# Mozard_Grounded_Touch_Pads.net
KiCad netlist of a schematic drawn in EAGLE
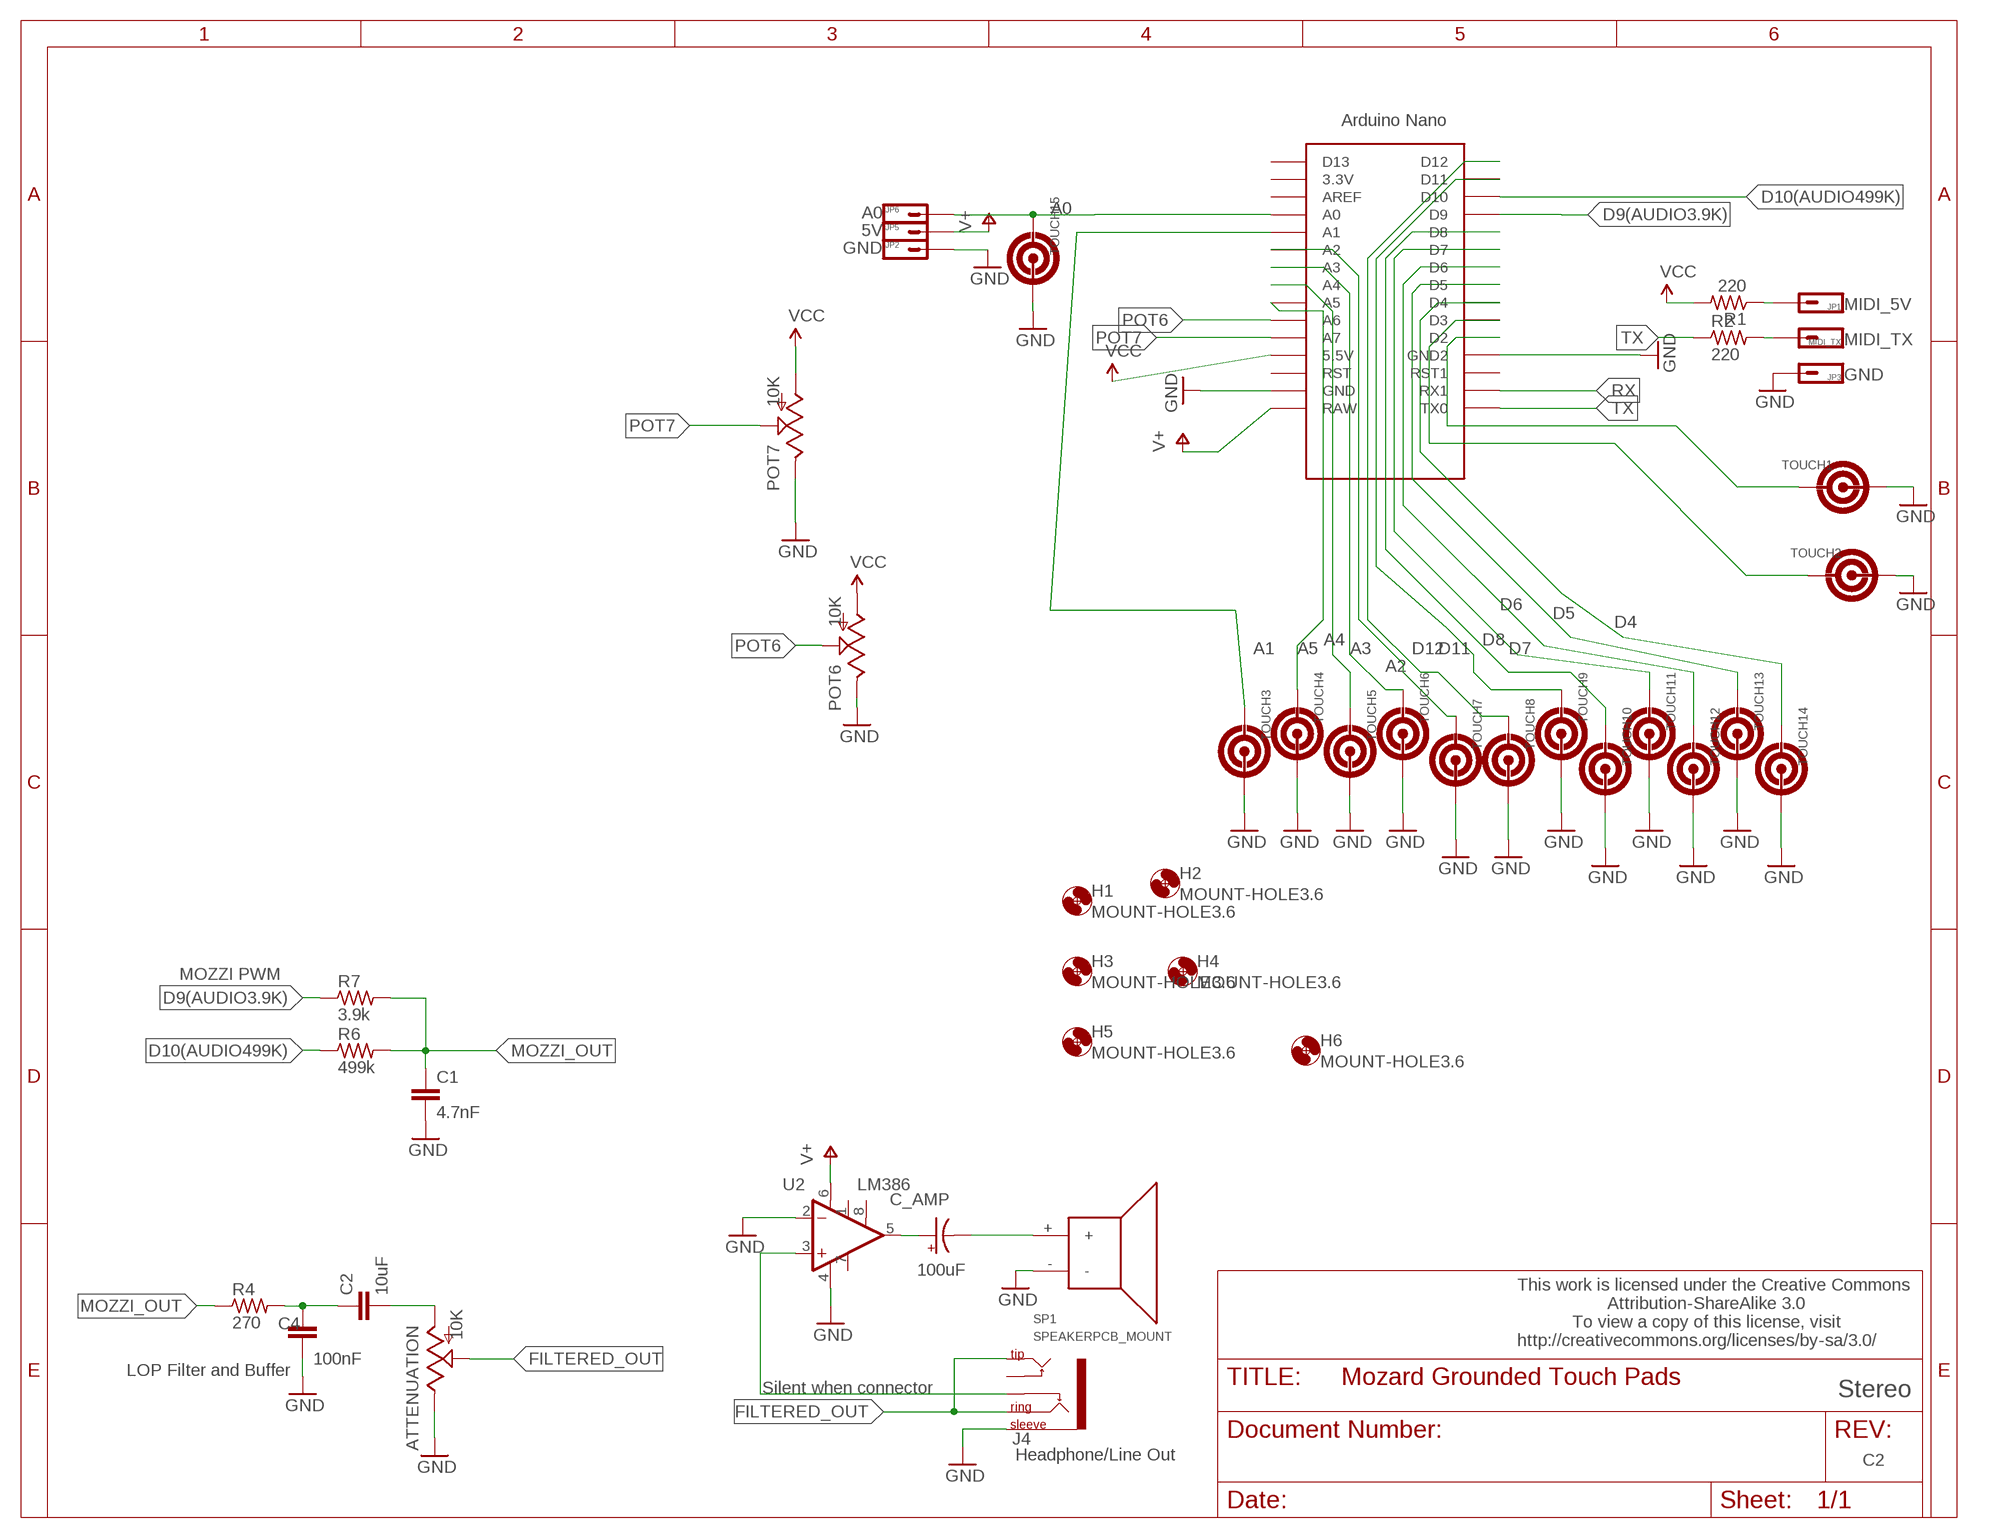
[diagram p0: schematic, sheet 1]

(export (version "E")
  (design (tool "Eeschema 10.0.6"))
  (components
    (comp (ref "ATTENUATION")
      (value "10K")
      (footprint "eagle-import:ALPS_POT_KIT")
      (libsource (lib "eagle-import") (part "POTALPS-KIT"))
    )
    (comp (ref "C1")
      (value "4.7nF")
      (footprint "eagle-import:CAP-PTH-SMALL-KIT")
      (libsource (lib "eagle-import") (part "0.1UF-50V-20%(PTH)KIT-EZ"))
    )
    (comp (ref "C2")
      (value "10uF")
      (footprint "eagle-import:CAP-PTH-SMALL-KIT")
      (libsource (lib "eagle-import") (part "0.1UF-50V-20%(PTH)KIT-EZ"))
    )
    (comp (ref "C4")
      (value "100nF")
      (footprint "eagle-import:CAP-PTH-SMALL-KIT")
      (libsource (lib "eagle-import") (part "0.1UF-50V-20%(PTH)KIT-EZ"))
    )
    (comp (ref "C_AMP")
      (value "100uF")
      (footprint "eagle-import:CPOL-RADIAL-10UF-25V")
      (libsource (lib "eagle-import") (part "CPOL-RADIAL-10UF-25V"))
    )
    (comp (ref "H1")
      (value "MOUNT-HOLE3.6")
      (footprint "eagle-import:3,6")
      (libsource (lib "eagle-import") (part "MOUNT-HOLE3.6"))
    )
    (comp (ref "H2")
      (value "MOUNT-HOLE3.6")
      (footprint "eagle-import:3,6")
      (libsource (lib "eagle-import") (part "MOUNT-HOLE3.6"))
    )
    (comp (ref "H3")
      (value "MOUNT-HOLE3.6")
      (footprint "eagle-import:3,6")
      (libsource (lib "eagle-import") (part "MOUNT-HOLE3.6"))
    )
    (comp (ref "H4")
      (value "MOUNT-HOLE3.6")
      (footprint "eagle-import:3,6")
      (libsource (lib "eagle-import") (part "MOUNT-HOLE3.6"))
    )
    (comp (ref "H5")
      (value "MOUNT-HOLE3.6")
      (footprint "eagle-import:3,6")
      (libsource (lib "eagle-import") (part "MOUNT-HOLE3.6"))
    )
    (comp (ref "H6")
      (value "MOUNT-HOLE3.6")
      (footprint "eagle-import:3,6")
      (libsource (lib "eagle-import") (part "MOUNT-HOLE3.6"))
    )
    (comp (ref "J4")
      (value "Headphone/Line Out")
      (footprint "eagle-import:AUDIO-JACK")
      (libsource (lib "eagle-import") (part "AUDIO-JACKPTH"))
    )
    (comp (ref "JP1")
      (value "MIDI_5V")
      (footprint "eagle-import:1X01_SIDE_NAME")
      (libsource (lib "eagle-import") (part "HEADER-1X1"))
    )
    (comp (ref "JP2")
      (value "GND")
      (footprint "eagle-import:1X01_SIDE_NAME")
      (libsource (lib "eagle-import") (part "HEADER-1X1"))
    )
    (comp (ref "JP3")
      (value "GND")
      (footprint "eagle-import:1X01_SIDE_NAME")
      (libsource (lib "eagle-import") (part "HEADER-1X1"))
    )
    (comp (ref "JP5")
      (value "5V")
      (footprint "eagle-import:1X01_SIDE_NAME")
      (libsource (lib "eagle-import") (part "HEADER-1X1"))
    )
    (comp (ref "JP6")
      (value "A0")
      (footprint "eagle-import:1X01_SIDE_NAME")
      (libsource (lib "eagle-import") (part "HEADER-1X1"))
    )
    (comp (ref "MIDI_TX")
      (value "MIDI_TX")
      (footprint "eagle-import:1X01_SIDE_NAME")
      (libsource (lib "eagle-import") (part "HEADER-1X1"))
    )
    (comp (ref "POT6")
      (value "10K")
      (footprint "eagle-import:ALPS_POT_KIT")
      (libsource (lib "eagle-import") (part "POTALPS-KIT"))
    )
    (comp (ref "POT7")
      (value "10K")
      (footprint "eagle-import:ALPS_POT_KIT")
      (libsource (lib "eagle-import") (part "POTALPS-KIT"))
    )
    (comp (ref "R1")
      (value "220")
      (footprint "eagle-import:0204_7")
      (libsource (lib "eagle-import") (part "R-US_0204/7"))
    )
    (comp (ref "R2")
      (value "220")
      (footprint "eagle-import:0204_7")
      (libsource (lib "eagle-import") (part "R-US_0204/7"))
    )
    (comp (ref "R4")
      (value "270")
      (footprint "eagle-import:0204_7")
      (libsource (lib "eagle-import") (part "R-US_0204/7"))
    )
    (comp (ref "R6")
      (value "499k")
      (footprint "eagle-import:0204_7")
      (libsource (lib "eagle-import") (part "R-US_0204/7"))
    )
    (comp (ref "R7")
      (value "3.9k")
      (footprint "eagle-import:0204_7")
      (libsource (lib "eagle-import") (part "R-US_0204/7"))
    )
    (comp (ref "SP1")
      (value "SPEAKERPCB_MOUNT")
      (footprint "eagle-import:PCB_MOUNT_SPEAKER")
      (fields (field (name "MFG") "SANCO"))
      (libsource (lib "eagle-import") (part "SPEAKERPCB_MOUNT"))
    )
    (comp (ref "TOUCH1")
      (value "PCB-TOUCHPAD2")
      (footprint "eagle-import:PCB-TOUCHPAD2")
      (libsource (lib "eagle-import") (part "PCB-TOUCHPAD2"))
    )
    (comp (ref "TOUCH2")
      (value "PCB-TOUCHPAD2")
      (footprint "eagle-import:PCB-TOUCHPAD2")
      (libsource (lib "eagle-import") (part "PCB-TOUCHPAD2"))
    )
    (comp (ref "TOUCH3")
      (value "PCB-TOUCHPAD2")
      (footprint "eagle-import:PCB-TOUCHPAD2")
      (libsource (lib "eagle-import") (part "PCB-TOUCHPAD2"))
    )
    (comp (ref "TOUCH4")
      (value "PCB-TOUCHPAD2")
      (footprint "eagle-import:PCB-TOUCHPAD2")
      (libsource (lib "eagle-import") (part "PCB-TOUCHPAD2"))
    )
    (comp (ref "TOUCH5")
      (value "PCB-TOUCHPAD2")
      (footprint "eagle-import:PCB-TOUCHPAD2")
      (libsource (lib "eagle-import") (part "PCB-TOUCHPAD2"))
    )
    (comp (ref "TOUCH6")
      (value "PCB-TOUCHPAD2")
      (footprint "eagle-import:PCB-TOUCHPAD2")
      (libsource (lib "eagle-import") (part "PCB-TOUCHPAD2"))
    )
    (comp (ref "TOUCH7")
      (value "PCB-TOUCHPAD2")
      (footprint "eagle-import:PCB-TOUCHPAD2")
      (libsource (lib "eagle-import") (part "PCB-TOUCHPAD2"))
    )
    (comp (ref "TOUCH8")
      (value "PCB-TOUCHPAD2")
      (footprint "eagle-import:PCB-TOUCHPAD2")
      (libsource (lib "eagle-import") (part "PCB-TOUCHPAD2"))
    )
    (comp (ref "TOUCH9")
      (value "PCB-TOUCHPAD2")
      (footprint "eagle-import:PCB-TOUCHPAD2")
      (libsource (lib "eagle-import") (part "PCB-TOUCHPAD2"))
    )
    (comp (ref "TOUCH10")
      (value "PCB-TOUCHPAD2")
      (footprint "eagle-import:PCB-TOUCHPAD2")
      (libsource (lib "eagle-import") (part "PCB-TOUCHPAD2"))
    )
    (comp (ref "TOUCH11")
      (value "PCB-TOUCHPAD2")
      (footprint "eagle-import:PCB-TOUCHPAD2")
      (libsource (lib "eagle-import") (part "PCB-TOUCHPAD2"))
    )
    (comp (ref "TOUCH12")
      (value "PCB-TOUCHPAD2")
      (footprint "eagle-import:PCB-TOUCHPAD2")
      (libsource (lib "eagle-import") (part "PCB-TOUCHPAD2"))
    )
    (comp (ref "TOUCH13")
      (value "PCB-TOUCHPAD2")
      (footprint "eagle-import:PCB-TOUCHPAD2")
      (libsource (lib "eagle-import") (part "PCB-TOUCHPAD2"))
    )
    (comp (ref "TOUCH14")
      (value "PCB-TOUCHPAD2")
      (footprint "eagle-import:PCB-TOUCHPAD2")
      (libsource (lib "eagle-import") (part "PCB-TOUCHPAD2"))
    )
    (comp (ref "TOUCH15")
      (value "PCB-TOUCHPAD2")
      (footprint "eagle-import:PCB-TOUCHPAD2")
      (libsource (lib "eagle-import") (part "PCB-TOUCHPAD2"))
    )
    (comp (ref "U$1")
      (value "NANO")
      (footprint "eagle-import:NANO")
      (libsource (lib "eagle-import") (part "NANO"))
    )
    (comp (ref "U2")
      (value "LM386")
      (footprint "eagle-import:DIP08")
      (libsource (lib "eagle-import") (part "LM386"))
    )
  )
  (nets
    (net (code "1") (name "/A0") (class "Default")
      (node (ref "JP6") (pin "1") (pinfunction "1_1") (pintype "passive"))
      (node (ref "TOUCH15") (pin "1") (pinfunction "1_1") (pintype "bidirectional"))
      (node (ref "U$1") (pin "A0") (pinfunction "A0_A0") (pintype "bidirectional"))
    )
    (net (code "2") (name "/A1") (class "Default")
      (node (ref "TOUCH3") (pin "1") (pinfunction "1_1") (pintype "bidirectional"))
      (node (ref "U$1") (pin "A1") (pinfunction "A1_A1") (pintype "bidirectional"))
    )
    (net (code "3") (name "/A2") (class "Default")
      (node (ref "TOUCH7") (pin "1") (pinfunction "1_1") (pintype "bidirectional"))
      (node (ref "U$1") (pin "A2") (pinfunction "A2_A2") (pintype "bidirectional"))
    )
    (net (code "4") (name "/A3") (class "Default")
      (node (ref "TOUCH6") (pin "1") (pinfunction "1_1") (pintype "bidirectional"))
      (node (ref "U$1") (pin "A3") (pinfunction "A3_A3") (pintype "bidirectional"))
    )
    (net (code "5") (name "/A4") (class "Default")
      (node (ref "TOUCH5") (pin "1") (pinfunction "1_1") (pintype "bidirectional"))
      (node (ref "U$1") (pin "A4") (pinfunction "A4_A4") (pintype "bidirectional"))
    )
    (net (code "6") (name "/A5") (class "Default")
      (node (ref "TOUCH4") (pin "1") (pinfunction "1_1") (pintype "bidirectional"))
      (node (ref "U$1") (pin "A5") (pinfunction "A5_A5") (pintype "bidirectional"))
    )
    (net (code "7") (name "/D4") (class "Default")
      (node (ref "TOUCH14") (pin "1") (pinfunction "1_1") (pintype "bidirectional"))
      (node (ref "U$1") (pin "D4") (pinfunction "D4_D4") (pintype "bidirectional"))
    )
    (net (code "8") (name "/D5") (class "Default")
      (node (ref "TOUCH13") (pin "1") (pinfunction "1_1") (pintype "bidirectional"))
      (node (ref "U$1") (pin "D5") (pinfunction "D5_D5") (pintype "bidirectional"))
    )
    (net (code "9") (name "/D6") (class "Default")
      (node (ref "TOUCH12") (pin "1") (pinfunction "1_1") (pintype "bidirectional"))
      (node (ref "U$1") (pin "D6") (pinfunction "D6_D6") (pintype "bidirectional"))
    )
    (net (code "10") (name "/D7") (class "Default")
      (node (ref "TOUCH11") (pin "1") (pinfunction "1_1") (pintype "bidirectional"))
      (node (ref "U$1") (pin "D7") (pinfunction "D7_D7") (pintype "bidirectional"))
    )
    (net (code "11") (name "/D8") (class "Default")
      (node (ref "TOUCH10") (pin "1") (pinfunction "1_1") (pintype "bidirectional"))
      (node (ref "U$1") (pin "D8") (pinfunction "D8_D8") (pintype "bidirectional"))
    )
    (net (code "12") (name "/D11") (class "Default")
      (node (ref "TOUCH9") (pin "1") (pinfunction "1_1") (pintype "bidirectional"))
      (node (ref "U$1") (pin "D11") (pinfunction "D11_D11") (pintype "bidirectional"))
    )
    (net (code "13") (name "/D12") (class "Default")
      (node (ref "TOUCH8") (pin "1") (pinfunction "1_1") (pintype "bidirectional"))
      (node (ref "U$1") (pin "D12") (pinfunction "D12_D12") (pintype "bidirectional"))
    )
    (net (code "14") (name "D9(AUDIO3.9K)") (class "Default")
      (node (ref "R7") (pin "1") (pinfunction "1_1") (pintype "passive"))
      (node (ref "U$1") (pin "D9") (pinfunction "D9_D9") (pintype "bidirectional"))
    )
    (net (code "15") (name "D10(AUDIO499K)") (class "Default")
      (node (ref "R6") (pin "1") (pinfunction "1_1") (pintype "passive"))
      (node (ref "U$1") (pin "D10") (pinfunction "D10_D10") (pintype "bidirectional"))
    )
    (net (code "16") (name "FILTERED_OUT") (class "Default")
      (node (ref "ATTENUATION") (pin "P$2") (pinfunction "S_P$2") (pintype "passive"))
      (node (ref "J4") (pin "RING") (pinfunction "RING_RING") (pintype "bidirectional"))
      (node (ref "J4") (pin "TIP") (pinfunction "TIP_TIP") (pintype "bidirectional"))
    )
    (net (code "17") (name "GND") (class "Default")
      (node (ref "ATTENUATION") (pin "P$1") (pinfunction "E_P$1") (pintype "passive"))
      (node (ref "C1") (pin "2") (pinfunction "2_2") (pintype "passive"))
      (node (ref "C4") (pin "2") (pinfunction "2_2") (pintype "passive"))
      (node (ref "J4") (pin "SLEEVE") (pinfunction "SLEEVE_SLEEVE") (pintype "bidirectional"))
      (node (ref "JP2") (pin "1") (pinfunction "1_1") (pintype "passive"))
      (node (ref "JP3") (pin "1") (pinfunction "1_1") (pintype "passive"))
      (node (ref "POT6") (pin "P$1") (pinfunction "E_P$1") (pintype "passive"))
      (node (ref "POT7") (pin "P$1") (pinfunction "E_P$1") (pintype "passive"))
      (node (ref "SP1") (pin "-") (pinfunction "-_-") (pintype "bidirectional"))
      (node (ref "TOUCH1") (pin "2") (pinfunction "2_2") (pintype "bidirectional"))
      (node (ref "TOUCH10") (pin "2") (pinfunction "2_2") (pintype "bidirectional"))
      (node (ref "TOUCH11") (pin "2") (pinfunction "2_2") (pintype "bidirectional"))
      (node (ref "TOUCH12") (pin "2") (pinfunction "2_2") (pintype "bidirectional"))
      (node (ref "TOUCH13") (pin "2") (pinfunction "2_2") (pintype "bidirectional"))
      (node (ref "TOUCH14") (pin "2") (pinfunction "2_2") (pintype "bidirectional"))
      (node (ref "TOUCH15") (pin "2") (pinfunction "2_2") (pintype "bidirectional"))
      (node (ref "TOUCH2") (pin "2") (pinfunction "2_2") (pintype "bidirectional"))
      (node (ref "TOUCH3") (pin "2") (pinfunction "2_2") (pintype "bidirectional"))
      (node (ref "TOUCH4") (pin "2") (pinfunction "2_2") (pintype "bidirectional"))
      (node (ref "TOUCH5") (pin "2") (pinfunction "2_2") (pintype "bidirectional"))
      (node (ref "TOUCH6") (pin "2") (pinfunction "2_2") (pintype "bidirectional"))
      (node (ref "TOUCH7") (pin "2") (pinfunction "2_2") (pintype "bidirectional"))
      (node (ref "TOUCH8") (pin "2") (pinfunction "2_2") (pintype "bidirectional"))
      (node (ref "TOUCH9") (pin "2") (pinfunction "2_2") (pintype "bidirectional"))
      (node (ref "U$1") (pin "GND") (pinfunction "GND_GND") (pintype "bidirectional"))
      (node (ref "U$1") (pin "GND1") (pinfunction "GND2_GND1") (pintype "bidirectional"))
      (node (ref "U2") (pin "2") (pinfunction "-IN_2") (pintype "input"))
      (node (ref "U2") (pin "4") (pinfunction "V-_4") (pintype "power_in"))
    )
    (net (code "18") (name "MOZZI_OUT") (class "Default")
      (node (ref "C1") (pin "1") (pinfunction "1_1") (pintype "passive"))
      (node (ref "R4") (pin "1") (pinfunction "1_1") (pintype "passive"))
      (node (ref "R6") (pin "2") (pinfunction "2_2") (pintype "passive"))
      (node (ref "R7") (pin "2") (pinfunction "2_2") (pintype "passive"))
    )
    (net (code "19") (name "Net-(ATTENUATION-A)") (class "Default")
      (node (ref "ATTENUATION") (pin "P$3") (pinfunction "A_P$3") (pintype "passive"))
      (node (ref "C2") (pin "2") (pinfunction "2_2") (pintype "passive"))
    )
    (net (code "20") (name "Net-(C2-Pad1)") (class "Default")
      (node (ref "C2") (pin "1") (pinfunction "1_1") (pintype "passive"))
      (node (ref "C4") (pin "1") (pinfunction "1_1") (pintype "passive"))
      (node (ref "R4") (pin "2") (pinfunction "2_2") (pintype "passive"))
    )
    (net (code "21") (name "Net-(C_AMP-Pad-)") (class "Default")
      (node (ref "C_AMP") (pin "-") (pinfunction "-_-") (pintype "passive"))
      (node (ref "SP1") (pin "+") (pinfunction "+_+") (pintype "bidirectional"))
    )
    (net (code "22") (name "Net-(JP1-Pad1)") (class "Default")
      (node (ref "JP1") (pin "1") (pinfunction "1_1") (pintype "passive"))
      (node (ref "R1") (pin "1") (pinfunction "1_1") (pintype "passive"))
    )
    (net (code "23") (name "Net-(MIDI_TX-Pad1)") (class "Default")
      (node (ref "MIDI_TX") (pin "1") (pinfunction "1_1") (pintype "passive"))
      (node (ref "R2") (pin "2") (pinfunction "2_2") (pintype "passive"))
    )
    (net (code "24") (name "Net-(TOUCH1-Pad1)") (class "Default")
      (node (ref "TOUCH1") (pin "1") (pinfunction "1_1") (pintype "bidirectional"))
      (node (ref "U$1") (pin "D2") (pinfunction "D2_D2") (pintype "bidirectional"))
    )
    (net (code "25") (name "Net-(TOUCH2-Pad1)") (class "Default")
      (node (ref "TOUCH2") (pin "1") (pinfunction "1_1") (pintype "bidirectional"))
      (node (ref "U$1") (pin "D3") (pinfunction "D3_D3") (pintype "bidirectional"))
    )
    (net (code "26") (name "Net-(U2-+IN)") (class "Default")
      (node (ref "J4") (pin "RSH") (pinfunction "RSH_RSH") (pintype "bidirectional"))
      (node (ref "U2") (pin "3") (pinfunction "+IN_3") (pintype "input"))
    )
    (net (code "27") (name "Net-(U2-OUT)") (class "Default")
      (node (ref "C_AMP") (pin "+") (pinfunction "+_+") (pintype "passive"))
      (node (ref "U2") (pin "5") (pinfunction "OUT_5") (pintype "output"))
    )
    (net (code "28") (name "POT6") (class "Default")
      (node (ref "POT6") (pin "P$2") (pinfunction "S_P$2") (pintype "passive"))
      (node (ref "U$1") (pin "A6") (pinfunction "A6_A6") (pintype "bidirectional"))
    )
    (net (code "29") (name "POT7") (class "Default")
      (node (ref "POT7") (pin "P$2") (pinfunction "S_P$2") (pintype "passive"))
      (node (ref "U$1") (pin "A7") (pinfunction "A7_A7") (pintype "bidirectional"))
    )
    (net (code "30") (name "RX") (class "Default")
      (node (ref "U$1") (pin "RX1") (pinfunction "RX1_RX1") (pintype "bidirectional"))
    )
    (net (code "31") (name "TX") (class "Default")
      (node (ref "R2") (pin "1") (pinfunction "1_1") (pintype "passive"))
      (node (ref "U$1") (pin "TX0") (pinfunction "TX0_TX0") (pintype "bidirectional"))
    )
    (net (code "32") (name "V+") (class "Default")
      (node (ref "JP5") (pin "1") (pinfunction "1_1") (pintype "passive"))
      (node (ref "U$1") (pin "RAW") (pinfunction "RAW_RAW") (pintype "bidirectional"))
      (node (ref "U2") (pin "6") (pinfunction "V+_6") (pintype "power_in"))
    )
    (net (code "33") (name "VCC") (class "Default")
      (node (ref "POT6") (pin "P$3") (pinfunction "A_P$3") (pintype "passive"))
      (node (ref "POT7") (pin "P$3") (pinfunction "A_P$3") (pintype "passive"))
      (node (ref "R1") (pin "2") (pinfunction "2_2") (pintype "passive"))
      (node (ref "U$1") (pin "5V") (pinfunction "5.5V_5V") (pintype "bidirectional"))
    )
    (net (code "34") (name "unconnected-(J4-PadTSH)") (class "Default")
      (node (ref "J4") (pin "TSH") (pinfunction "TSH_TSH") (pintype "bidirectional"))
    )
    (net (code "35") (name "unconnected-(U$1-Pad3.3V)") (class "Default")
      (node (ref "U$1") (pin "3.3V") (pinfunction "3.3V_3.3V") (pintype "bidirectional"))
    )
    (net (code "36") (name "unconnected-(U$1-PadAREF)") (class "Default")
      (node (ref "U$1") (pin "AREF") (pinfunction "AREF_AREF") (pintype "bidirectional"))
    )
    (net (code "37") (name "unconnected-(U$1-PadD13)") (class "Default")
      (node (ref "U$1") (pin "D13") (pinfunction "D13_D13") (pintype "bidirectional"))
    )
    (net (code "38") (name "unconnected-(U$1-PadRST)") (class "Default")
      (node (ref "U$1") (pin "RST") (pinfunction "RST_RST") (pintype "bidirectional"))
    )
    (net (code "39") (name "unconnected-(U$1-PadRST1)") (class "Default")
      (node (ref "U$1") (pin "RST1") (pinfunction "RST1_RST1") (pintype "bidirectional"))
    )
    (net (code "40") (name "unconnected-(U2-BP-Pad7)") (class "Default")
      (node (ref "U2") (pin "7") (pinfunction "BP_7") (pintype "bidirectional"))
    )
    (net (code "41") (name "unconnected-(U2-GAIN-Pad1)") (class "Default")
      (node (ref "U2") (pin "1") (pinfunction "GAIN_1") (pintype "bidirectional"))
    )
    (net (code "42") (name "unconnected-(U2-GAIN-Pad8)") (class "Default")
      (node (ref "U2") (pin "8") (pinfunction "GAIN_8") (pintype "bidirectional"))
    )
  )
)
